# Sheet1.net
KiCad netlist of a schematic drawn in Altium Designer
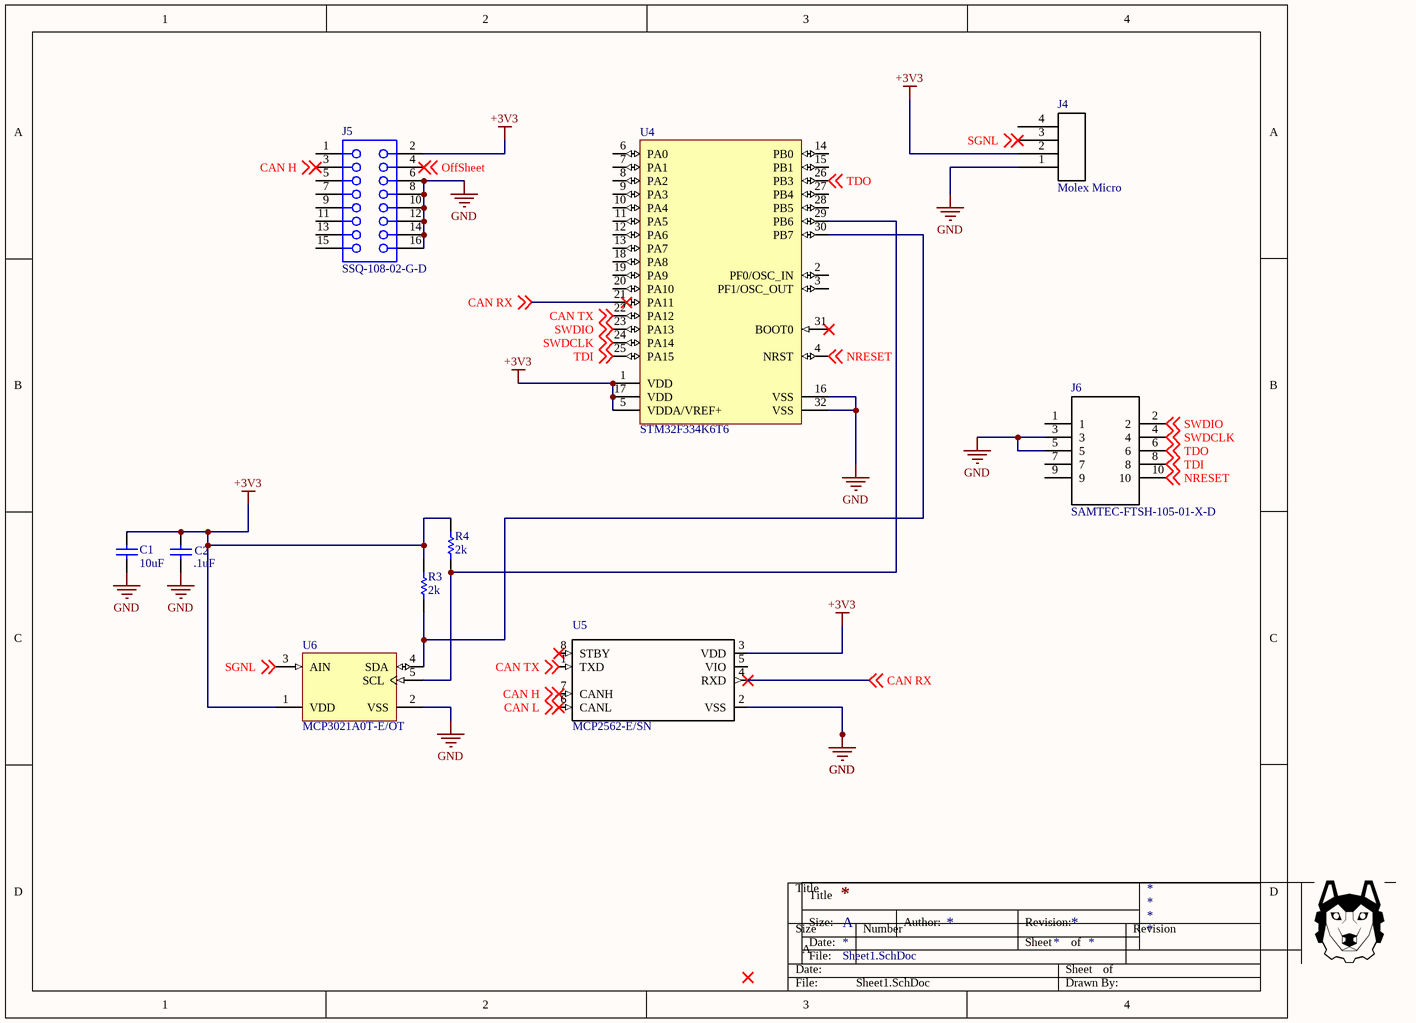
[diagram p0: Sheet1.SchDoc]

(export (version "E")
  (design (tool "Eeschema 10.0.6"))
  (components
    (comp (ref "C1")
      (value "10uF")
      (footprint "Cap 0805")
      (description "Standard Capacitor")
      (fields (field (name "MANUFACTURER") "AVX"))
      (libsource (lib "Husky Robotics Standard Library 2019-2020") (part "Capacitor 0805"))
    )
    (comp (ref "C2")
      (value ".1uF")
      (footprint "Cap 0805")
      (description "Standard Capacitor")
      (fields (field (name "MANUFACTURER") "AVX"))
      (libsource (lib "Husky Robotics Standard Library 2019-2020") (part "Capacitor 0805"))
    )
    (comp (ref "J4")
      (value "Molex Micro")
      (footprint "0430450427")
      (description "Molex micro-fit 3.0 dual row header. P/N 0430450427")
      (libsource (lib "Husky Robotics Standard Library 2019-2020") (part "Molex micro-fit 4-pin (Single row schematic)"))
    )
    (comp (ref "J5")
      (value "SSQ-108-02-G-D")
      (footprint "SMTC-SSQ-108-02-X-D")
      (description "SQ Post Socket, Through-hole, Vertical, -55 to 125 degC, 2.54 mm Pitch, 16-Pin, Female, RoHS")
      (fields (field (name "MANUFACTURER") "Samtec"))
      (libsource (lib "Husky Robotics Standard Library 2019-2020") (part "CMP-1023-00300-1"))
    )
    (comp (ref "J6")
      (value "SAMTEC-FTSH-105-01-X-D")
      (footprint "SAMTEC-FTSH-105-01-X-D")
      (libsource (lib "Husky Robotics Standard Library 2019-2020") (part "SAMTEC-FTSH-105-01-X-D"))
    )
    (comp (ref "R3")
      (value "2k")
      (footprint "RESC0805(2012)_N")
      (description "120R 0.125W 5% 0805 (2012 Metric)  SMD")
      (fields (field (name "TOLERANCE") "5 %") (field (name "POWER") "0.125 W"))
      (libsource (lib "Husky Robotics Standard Library 2019-2020") (part "120R 5% 0805"))
    )
    (comp (ref "R4")
      (value "2k")
      (footprint "RESC0805(2012)_N")
      (description "120R 0.125W 5% 0805 (2012 Metric)  SMD")
      (fields (field (name "TOLERANCE") "5 %") (field (name "POWER") "0.125 W"))
      (libsource (lib "Husky Robotics Standard Library 2019-2020") (part "120R 5% 0805"))
    )
    (comp (ref "U4")
      (value "STM32F334K6T6")
      (footprint "STM-LQFP32_N")
      (libsource (lib "Husky Robotics Standard Library 2019-2020") (part "STM32F334K6T6"))
    )
    (comp (ref "U5")
      (value "MCP2562-E/SN")
      (footprint "SOIC127P600X175-8N")
      (description "Microchip MCP2562-E/SN, CAN Transceiver 1MBps 1-channel IEC 61000-4-2, 8-Pin SOIC")
      (fields (field (name "MF") "Microchip"))
      (libsource (lib "Husky Robotics Standard Library 2019-2020") (part "CAN Tranceiver"))
    )
    (comp (ref "U6")
      (value "MCP3021A0T-E/OT")
      (footprint "SOT-23-OT5_M")
      (libsource (lib "Components - 04.04.20 - 12.43") (part "CMP-0188-01214-1"))
    )
  )
  (nets
    (net (code "1") (name "+3V3") (class "Default")
      (node (ref "C1") (pin "2") (pinfunction "2_2") (pintype "passive"))
      (node (ref "C2") (pin "2") (pinfunction "2_2") (pintype "passive"))
      (node (ref "J4") (pin "2") (pintype "passive"))
      (node (ref "J5") (pin "2") (pinfunction "2_2") (pintype "passive"))
      (node (ref "R3") (pin "2") (pinfunction "2_2") (pintype "passive"))
      (node (ref "R4") (pin "2") (pinfunction "2_2") (pintype "passive"))
      (node (ref "U4") (pin "1") (pinfunction "VDD_1") (pintype "power_in"))
      (node (ref "U4") (pin "17") (pinfunction "VDD_17") (pintype "power_in"))
      (node (ref "U4") (pin "5") (pinfunction "VDDA/VREF+_5") (pintype "power_in"))
      (node (ref "U5") (pin "3") (pinfunction "VDD_3") (pintype "power_in"))
      (node (ref "U6") (pin "1") (pinfunction "VDD_1") (pintype "power_in"))
    )
    (net (code "2") (name "CAN H") (class "Default")
      (node (ref "J5") (pin "3") (pinfunction "3_3") (pintype "passive"))
      (node (ref "U5") (pin "7") (pinfunction "CANH_7") (pintype "input"))
    )
    (net (code "3") (name "CAN L") (class "Default")
      (node (ref "U5") (pin "6") (pinfunction "CANL_6") (pintype "input"))
    )
    (net (code "4") (name "CAN RX") (class "Default")
      (node (ref "U4") (pin "21") (pinfunction "PA11_21") (pintype "bidirectional"))
      (node (ref "U5") (pin "4") (pinfunction "RXD_4") (pintype "output"))
    )
    (net (code "5") (name "CAN TX") (class "Default")
      (node (ref "U4") (pin "22") (pinfunction "PA12_22") (pintype "bidirectional"))
      (node (ref "U5") (pin "1") (pinfunction "TXD_1") (pintype "input"))
    )
    (net (code "6") (name "GND") (class "Default")
      (node (ref "C1") (pin "1") (pinfunction "1_1") (pintype "passive"))
      (node (ref "C2") (pin "1") (pinfunction "1_1") (pintype "passive"))
      (node (ref "J4") (pin "1") (pintype "passive"))
      (node (ref "J5") (pin "10") (pinfunction "10_10") (pintype "passive"))
      (node (ref "J5") (pin "12") (pinfunction "12_12") (pintype "passive"))
      (node (ref "J5") (pin "14") (pinfunction "14_14") (pintype "passive"))
      (node (ref "J5") (pin "16") (pinfunction "16_16") (pintype "passive"))
      (node (ref "J5") (pin "6") (pinfunction "6_6") (pintype "passive"))
      (node (ref "J5") (pin "8") (pinfunction "8_8") (pintype "passive"))
      (node (ref "J6") (pin "3") (pinfunction "3_3") (pintype "passive"))
      (node (ref "J6") (pin "5") (pinfunction "5_5") (pintype "passive"))
      (node (ref "U4") (pin "16") (pinfunction "VSS_16") (pintype "power_in"))
      (node (ref "U4") (pin "32") (pinfunction "VSS_32") (pintype "power_in"))
      (node (ref "U5") (pin "2") (pinfunction "VSS_2") (pintype "power_in"))
      (node (ref "U6") (pin "2") (pinfunction "VSS_2") (pintype "power_in"))
    )
    (net (code "7") (name "NRESET") (class "Default")
      (node (ref "J6") (pin "10") (pinfunction "10_10") (pintype "passive"))
      (node (ref "U4") (pin "4") (pinfunction "NRST_4") (pintype "bidirectional"))
    )
    (net (code "8") (name "Net-(U4-PB6)") (class "Default")
      (node (ref "R4") (pin "1") (pinfunction "1_1") (pintype "passive"))
      (node (ref "U4") (pin "29") (pinfunction "PB6_29") (pintype "bidirectional"))
      (node (ref "U6") (pin "5") (pinfunction "SCL_5") (pintype "input"))
    )
    (net (code "9") (name "Net-(U4-PB7)") (class "Default")
      (node (ref "R3") (pin "1") (pinfunction "1_1") (pintype "passive"))
      (node (ref "U4") (pin "30") (pinfunction "PB7_30") (pintype "bidirectional"))
      (node (ref "U6") (pin "4") (pinfunction "SDA_4") (pintype "bidirectional"))
    )
    (net (code "10") (name "OffSheet") (class "Default")
      (node (ref "J5") (pin "4") (pinfunction "4_4") (pintype "passive"))
    )
    (net (code "11") (name "SGNL") (class "Default")
      (node (ref "J4") (pin "3") (pintype "passive"))
      (node (ref "U6") (pin "3") (pinfunction "AIN_3") (pintype "input"))
    )
    (net (code "12") (name "SWDCLK") (class "Default")
      (node (ref "J6") (pin "4") (pinfunction "4_4") (pintype "passive"))
      (node (ref "U4") (pin "24") (pinfunction "PA14_24") (pintype "bidirectional"))
    )
    (net (code "13") (name "SWDIO") (class "Default")
      (node (ref "J6") (pin "2") (pinfunction "2_2") (pintype "passive"))
      (node (ref "U4") (pin "23") (pinfunction "PA13_23") (pintype "bidirectional"))
    )
    (net (code "14") (name "TDI") (class "Default")
      (node (ref "J6") (pin "8") (pinfunction "8_8") (pintype "passive"))
      (node (ref "U4") (pin "25") (pinfunction "PA15_25") (pintype "bidirectional"))
    )
    (net (code "15") (name "TDO") (class "Default")
      (node (ref "J6") (pin "6") (pinfunction "6_6") (pintype "passive"))
      (node (ref "U4") (pin "26") (pinfunction "PB3_26") (pintype "bidirectional"))
    )
    (net (code "16") (name "unconnected-(J4-Pad4)") (class "Default")
      (node (ref "J4") (pin "4") (pintype "passive"))
    )
    (net (code "17") (name "unconnected-(J5-Pad1)") (class "Default")
      (node (ref "J5") (pin "1") (pinfunction "1_1") (pintype "passive"))
    )
    (net (code "18") (name "unconnected-(J5-Pad5)") (class "Default")
      (node (ref "J5") (pin "5") (pinfunction "5_5") (pintype "passive"))
    )
    (net (code "19") (name "unconnected-(J5-Pad7)") (class "Default")
      (node (ref "J5") (pin "7") (pinfunction "7_7") (pintype "passive"))
    )
    (net (code "20") (name "unconnected-(J5-Pad9)") (class "Default")
      (node (ref "J5") (pin "9") (pinfunction "9_9") (pintype "passive"))
    )
    (net (code "21") (name "unconnected-(J5-Pad11)") (class "Default")
      (node (ref "J5") (pin "11") (pinfunction "11_11") (pintype "passive"))
    )
    (net (code "22") (name "unconnected-(J5-Pad13)") (class "Default")
      (node (ref "J5") (pin "13") (pinfunction "13_13") (pintype "passive"))
    )
    (net (code "23") (name "unconnected-(J5-Pad15)") (class "Default")
      (node (ref "J5") (pin "15") (pinfunction "15_15") (pintype "passive"))
    )
    (net (code "24") (name "unconnected-(J6-Pad1)") (class "Default")
      (node (ref "J6") (pin "1") (pinfunction "1_1") (pintype "passive"))
    )
    (net (code "25") (name "unconnected-(J6-Pad7)") (class "Default")
      (node (ref "J6") (pin "7") (pinfunction "7_7") (pintype "passive"))
    )
    (net (code "26") (name "unconnected-(J6-Pad9)") (class "Default")
      (node (ref "J6") (pin "9") (pinfunction "9_9") (pintype "passive"))
    )
    (net (code "27") (name "unconnected-(U4-BOOT0-Pad31)") (class "Default")
      (node (ref "U4") (pin "31") (pinfunction "BOOT0_31") (pintype "input+no_connect"))
    )
    (net (code "28") (name "unconnected-(U4-PA0-Pad6)") (class "Default")
      (node (ref "U4") (pin "6") (pinfunction "PA0_6") (pintype "bidirectional"))
    )
    (net (code "29") (name "unconnected-(U4-PA1-Pad7)") (class "Default")
      (node (ref "U4") (pin "7") (pinfunction "PA1_7") (pintype "bidirectional"))
    )
    (net (code "30") (name "unconnected-(U4-PA2-Pad8)") (class "Default")
      (node (ref "U4") (pin "8") (pinfunction "PA2_8") (pintype "bidirectional"))
    )
    (net (code "31") (name "unconnected-(U4-PA3-Pad9)") (class "Default")
      (node (ref "U4") (pin "9") (pinfunction "PA3_9") (pintype "bidirectional"))
    )
    (net (code "32") (name "unconnected-(U4-PA4-Pad10)") (class "Default")
      (node (ref "U4") (pin "10") (pinfunction "PA4_10") (pintype "bidirectional"))
    )
    (net (code "33") (name "unconnected-(U4-PA5-Pad11)") (class "Default")
      (node (ref "U4") (pin "11") (pinfunction "PA5_11") (pintype "bidirectional"))
    )
    (net (code "34") (name "unconnected-(U4-PA6-Pad12)") (class "Default")
      (node (ref "U4") (pin "12") (pinfunction "PA6_12") (pintype "bidirectional"))
    )
    (net (code "35") (name "unconnected-(U4-PA7-Pad13)") (class "Default")
      (node (ref "U4") (pin "13") (pinfunction "PA7_13") (pintype "bidirectional"))
    )
    (net (code "36") (name "unconnected-(U4-PA8-Pad18)") (class "Default")
      (node (ref "U4") (pin "18") (pinfunction "PA8_18") (pintype "bidirectional"))
    )
    (net (code "37") (name "unconnected-(U4-PA9-Pad19)") (class "Default")
      (node (ref "U4") (pin "19") (pinfunction "PA9_19") (pintype "bidirectional"))
    )
    (net (code "38") (name "unconnected-(U4-PA10-Pad20)") (class "Default")
      (node (ref "U4") (pin "20") (pinfunction "PA10_20") (pintype "bidirectional"))
    )
    (net (code "39") (name "unconnected-(U4-PB0-Pad14)") (class "Default")
      (node (ref "U4") (pin "14") (pinfunction "PB0_14") (pintype "bidirectional"))
    )
    (net (code "40") (name "unconnected-(U4-PB1-Pad15)") (class "Default")
      (node (ref "U4") (pin "15") (pinfunction "PB1_15") (pintype "bidirectional"))
    )
    (net (code "41") (name "unconnected-(U4-PB4-Pad27)") (class "Default")
      (node (ref "U4") (pin "27") (pinfunction "PB4_27") (pintype "bidirectional"))
    )
    (net (code "42") (name "unconnected-(U4-PB5-Pad28)") (class "Default")
      (node (ref "U4") (pin "28") (pinfunction "PB5_28") (pintype "bidirectional"))
    )
    (net (code "43") (name "unconnected-(U4-PF0{slash}OSC_IN-Pad2)") (class "Default")
      (node (ref "U4") (pin "2") (pinfunction "PF0/OSC_IN_2") (pintype "bidirectional"))
    )
    (net (code "44") (name "unconnected-(U4-PF1{slash}OSC_OUT-Pad3)") (class "Default")
      (node (ref "U4") (pin "3") (pinfunction "PF1/OSC_OUT_3") (pintype "bidirectional"))
    )
    (net (code "45") (name "unconnected-(U5-STBY-Pad8)") (class "Default")
      (node (ref "U5") (pin "8") (pinfunction "STBY_8") (pintype "input+no_connect"))
    )
    (net (code "46") (name "unconnected-(U5-VIO-Pad5)") (class "Default")
      (node (ref "U5") (pin "5") (pinfunction "VIO_5") (pintype "power_in"))
    )
  )
)
